# AR_-_Attack_Release.net
KiCad netlist of a schematic drawn in EAGLE
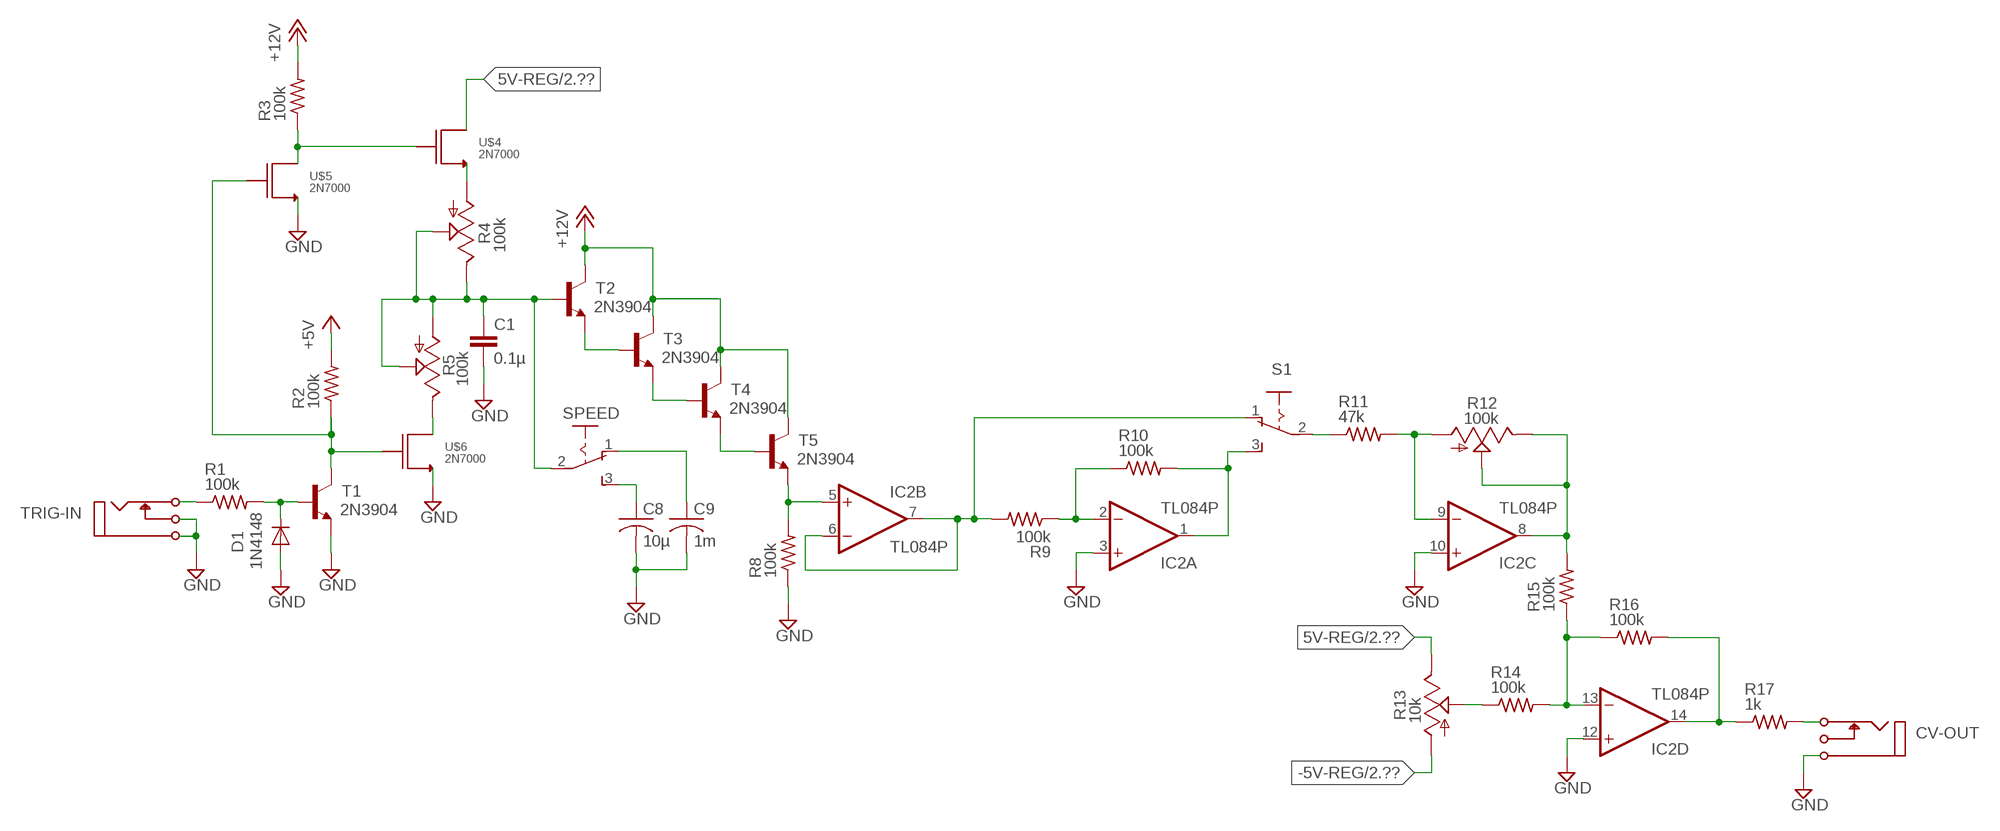
[diagram p0: schematic, sheet 1]
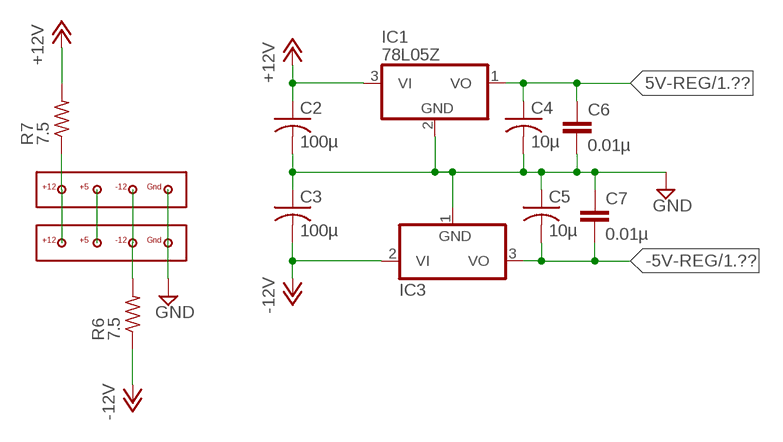
[diagram p1: schematic, sheet 2]

(export (version "E")
  (design (tool "Eeschema 10.0.6"))
  (components
    (comp (ref "C1")
      (value "0.1µ")
      (footprint "eagle-import:C2.5-2")
      (libsource (lib "eagle-import") (part "C2.5/2"))
    )
    (comp (ref "C8")
      (value "10µ")
      (footprint "eagle-import:C025-050X050")
      (libsource (lib "eagle-import") (part "C-US025-050X050"))
    )
    (comp (ref "C9")
      (value "1m")
      (footprint "eagle-import:C025-050X050")
      (libsource (lib "eagle-import") (part "C-US025-050X050"))
    )
    (comp (ref "CV-OUT")
      (value "I/O")
      (footprint "eagle-import:MONO_JACK")
      (libsource (lib "eagle-import") (part "MONO_JACK"))
    )
    (comp (ref "D1")
      (value "1N4148")
      (footprint "eagle-import:DO35-7")
      (libsource (lib "eagle-import") (part "1N4148DO35-7"))
    )
    (comp (ref "IC2")
      (value "TL084P")
      (footprint "eagle-import:DIL14")
      (libsource (lib "eagle-import") (part "TL084P"))
    )
    (comp (ref "R1")
      (value "100k")
      (footprint "eagle-import:0204_7")
      (libsource (lib "eagle-import") (part "R-US_0204/7"))
    )
    (comp (ref "R2")
      (value "100k")
      (footprint "eagle-import:0204_7")
      (libsource (lib "eagle-import") (part "R-US_0204/7"))
    )
    (comp (ref "R3")
      (value "100k")
      (footprint "eagle-import:0204_7")
      (libsource (lib "eagle-import") (part "R-US_0204/7"))
    )
    (comp (ref "R4")
      (value "100k")
      (footprint "eagle-import:B64Y")
      (libsource (lib "eagle-import") (part "TRIM_US-B64Y"))
    )
    (comp (ref "R5")
      (value "100k")
      (footprint "eagle-import:B64Y")
      (libsource (lib "eagle-import") (part "TRIM_US-B64Y"))
    )
    (comp (ref "R8")
      (value "100k")
      (footprint "eagle-import:0204_7")
      (libsource (lib "eagle-import") (part "R-US_0204/7"))
    )
    (comp (ref "R9")
      (value "100k")
      (footprint "eagle-import:0204_7")
      (libsource (lib "eagle-import") (part "R-US_0204/7"))
    )
    (comp (ref "R10")
      (value "100k")
      (footprint "eagle-import:0204_7")
      (libsource (lib "eagle-import") (part "R-US_0204/7"))
    )
    (comp (ref "R11")
      (value "47k")
      (footprint "eagle-import:0204_7")
      (libsource (lib "eagle-import") (part "R-US_0204/7"))
    )
    (comp (ref "R12")
      (value "100k")
      (footprint "eagle-import:B64Y")
      (libsource (lib "eagle-import") (part "TRIM_US-B64Y"))
    )
    (comp (ref "R13")
      (value "10k")
      (footprint "eagle-import:B64Y")
      (libsource (lib "eagle-import") (part "TRIM_US-B64Y"))
    )
    (comp (ref "R14")
      (value "100k")
      (footprint "eagle-import:0204_7")
      (libsource (lib "eagle-import") (part "R-US_0204/7"))
    )
    (comp (ref "R15")
      (value "100k")
      (footprint "eagle-import:0204_7")
      (libsource (lib "eagle-import") (part "R-US_0204/7"))
    )
    (comp (ref "R16")
      (value "100k")
      (footprint "eagle-import:0204_7")
      (libsource (lib "eagle-import") (part "R-US_0204/7"))
    )
    (comp (ref "R17")
      (value "1k")
      (footprint "eagle-import:0204_7")
      (libsource (lib "eagle-import") (part "R-US_0204/7"))
    )
    (comp (ref "S1")
      (value "255SB")
      (footprint "eagle-import:255SB")
      (libsource (lib "eagle-import") (part "255SB"))
    )
    (comp (ref "SPEED")
      (value "255SB")
      (footprint "eagle-import:255SB")
      (libsource (lib "eagle-import") (part "255SB"))
    )
    (comp (ref "T1")
      (value "2N3904")
      (footprint "eagle-import:TO92")
      (libsource (lib "eagle-import") (part "2N3904"))
    )
    (comp (ref "T2")
      (value "2N3904")
      (footprint "eagle-import:TO92")
      (libsource (lib "eagle-import") (part "2N3904"))
    )
    (comp (ref "T3")
      (value "2N3904")
      (footprint "eagle-import:TO92")
      (libsource (lib "eagle-import") (part "2N3904"))
    )
    (comp (ref "T4")
      (value "2N3904")
      (footprint "eagle-import:TO92")
      (libsource (lib "eagle-import") (part "2N3904"))
    )
    (comp (ref "T5")
      (value "2N3904")
      (footprint "eagle-import:TO92")
      (libsource (lib "eagle-import") (part "2N3904"))
    )
    (comp (ref "TRIG-IN")
      (value "I/O")
      (footprint "eagle-import:MONO_JACK")
      (libsource (lib "eagle-import") (part "MONO_JACK"))
    )
    (comp (ref "U$4")
      (value "2N7000")
      (footprint "eagle-import:2N7000")
      (libsource (lib "eagle-import") (part "2N7000"))
    )
    (comp (ref "U$5")
      (value "2N7000")
      (footprint "eagle-import:2N7000")
      (libsource (lib "eagle-import") (part "2N7000"))
    )
    (comp (ref "U$6")
      (value "2N7000")
      (footprint "eagle-import:2N7000")
      (libsource (lib "eagle-import") (part "2N7000"))
    )
    (comp (ref "C2")
      (value "100µ")
      (footprint "eagle-import:C025-050X050")
      (libsource (lib "eagle-import") (part "C-US025-050X050"))
    )
    (comp (ref "C3")
      (value "100µ")
      (footprint "eagle-import:C025-050X050")
      (libsource (lib "eagle-import") (part "C-US025-050X050"))
    )
    (comp (ref "C4")
      (value "10µ")
      (footprint "eagle-import:C025-050X050")
      (libsource (lib "eagle-import") (part "C-US025-050X050"))
    )
    (comp (ref "C5")
      (value "10µ")
      (footprint "eagle-import:C025-050X050")
      (libsource (lib "eagle-import") (part "C-US025-050X050"))
    )
    (comp (ref "C6")
      (value "0.01µ")
      (footprint "eagle-import:C2.5-2")
      (libsource (lib "eagle-import") (part "C2.5/2"))
    )
    (comp (ref "C7")
      (value "0.01µ")
      (footprint "eagle-import:C2.5-2")
      (libsource (lib "eagle-import") (part "C2.5/2"))
    )
    (comp (ref "IC1")
      (value "78L05Z")
      (footprint "eagle-import:TO92")
      (libsource (lib "eagle-import") (part "78ZL05"))
    )
    (comp (ref "IC3")
      (value "79L05Z")
      (footprint "eagle-import:TO92")
      (libsource (lib "eagle-import") (part "79ZL05"))
    )
    (comp (ref "R6")
      (value "7.5")
      (footprint "eagle-import:0204_7")
      (libsource (lib "eagle-import") (part "R-US_0204/7"))
    )
    (comp (ref "R7")
      (value "7.5")
      (footprint "eagle-import:0204_7")
      (libsource (lib "eagle-import") (part "R-US_0204/7"))
    )
    (comp (ref "U$3")
      (value "POWER_CONNECTOR_4_RGBB")
      (footprint "eagle-import:POWER_CONNECTOR_4_RGBB")
      (libsource (lib "eagle-import") (part "POWER_CONNECTOR_4_RGBB"))
    )
    (comp (ref "U$7")
      (value "POWER_CONNECTOR_4_RGBB")
      (footprint "eagle-import:POWER_CONNECTOR_4_RGBB")
      (libsource (lib "eagle-import") (part "POWER_CONNECTOR_4_RGBB"))
    )
  )
  (nets
    (net (code "1") (name "+5V") (class "Default")
      (node (ref "R2") (pin "2") (pinfunction "2_2") (pintype "passive"))
    )
    (net (code "2") (name "+12V") (class "Default")
      (node (ref "C2") (pin "1") (pinfunction "1_1") (pintype "passive"))
      (node (ref "IC1") (pin "3") (pinfunction "VI_3") (pintype "input"))
      (node (ref "R3") (pin "2") (pinfunction "2_2") (pintype "passive"))
      (node (ref "R7") (pin "2") (pinfunction "2_2") (pintype "passive"))
      (node (ref "T2") (pin "1") (pinfunction "C_1") (pintype "passive"))
      (node (ref "T3") (pin "1") (pinfunction "C_1") (pintype "passive"))
      (node (ref "T4") (pin "1") (pinfunction "C_1") (pintype "passive"))
      (node (ref "T5") (pin "1") (pinfunction "C_1") (pintype "passive"))
    )
    (net (code "3") (name "-5V-REG") (class "Default")
      (node (ref "C5") (pin "2") (pinfunction "2_2") (pintype "passive"))
      (node (ref "C7") (pin "2") (pinfunction "2_2") (pintype "passive"))
      (node (ref "IC3") (pin "3") (pinfunction "VO_3") (pintype "passive"))
      (node (ref "R13") (pin "A") (pinfunction "A_A") (pintype "passive"))
    )
    (net (code "4") (name "-12V") (class "Default")
      (node (ref "C3") (pin "2") (pinfunction "2_2") (pintype "passive"))
      (node (ref "IC3") (pin "2") (pinfunction "VI_2") (pintype "input"))
      (node (ref "R6") (pin "1") (pinfunction "1_1") (pintype "passive"))
    )
    (net (code "5") (name "5V-REG") (class "Default")
      (node (ref "C4") (pin "1") (pinfunction "1_1") (pintype "passive"))
      (node (ref "C6") (pin "1") (pinfunction "1_1") (pintype "passive"))
      (node (ref "IC1") (pin "1") (pinfunction "VO_1") (pintype "passive"))
      (node (ref "R13") (pin "E") (pinfunction "E_E") (pintype "passive"))
      (node (ref "U$4") (pin "D") (pinfunction "D_D") (pintype "bidirectional"))
    )
    (net (code "6") (name "GND") (class "Default")
      (node (ref "C1") (pin "2") (pinfunction "2_2") (pintype "passive"))
      (node (ref "C2") (pin "2") (pinfunction "2_2") (pintype "passive"))
      (node (ref "C3") (pin "1") (pinfunction "1_1") (pintype "passive"))
      (node (ref "C4") (pin "2") (pinfunction "2_2") (pintype "passive"))
      (node (ref "C5") (pin "1") (pinfunction "1_1") (pintype "passive"))
      (node (ref "C6") (pin "2") (pinfunction "2_2") (pintype "passive"))
      (node (ref "C7") (pin "1") (pinfunction "1_1") (pintype "passive"))
      (node (ref "C8") (pin "2") (pinfunction "2_2") (pintype "passive"))
      (node (ref "C9") (pin "2") (pinfunction "2_2") (pintype "passive"))
      (node (ref "CV-OUT") (pin "P$1") (pinfunction "P$1_P$1") (pintype "bidirectional"))
      (node (ref "D1") (pin "A") (pinfunction "A_A") (pintype "passive"))
      (node (ref "IC1") (pin "2") (pinfunction "GND_2") (pintype "passive"))
      (node (ref "IC2") (pin "10") (pinfunction "+IN_10") (pintype "input"))
      (node (ref "IC2") (pin "12") (pinfunction "+IN_12") (pintype "input"))
      (node (ref "IC2") (pin "3") (pinfunction "+IN_3") (pintype "input"))
      (node (ref "IC3") (pin "1") (pinfunction "GND_1") (pintype "passive"))
      (node (ref "R8") (pin "1") (pinfunction "1_1") (pintype "passive"))
      (node (ref "T1") (pin "3") (pinfunction "E_3") (pintype "passive"))
      (node (ref "TRIG-IN") (pin "P$1") (pinfunction "P$1_P$1") (pintype "bidirectional"))
      (node (ref "TRIG-IN") (pin "P$3") (pinfunction "P3_P$3") (pintype "bidirectional"))
      (node (ref "U$3") (pin "GND") (pinfunction "GND_GND") (pintype "bidirectional"))
      (node (ref "U$5") (pin "S") (pinfunction "S_S") (pintype "bidirectional"))
      (node (ref "U$6") (pin "S") (pinfunction "S_S") (pintype "bidirectional"))
      (node (ref "U$7") (pin "GND") (pinfunction "GND_GND") (pintype "bidirectional"))
    )
    (net (code "7") (name "Net-(CV-OUT-P2)") (class "Default")
      (node (ref "CV-OUT") (pin "P$2") (pinfunction "P2_P$2") (pintype "bidirectional"))
      (node (ref "R17") (pin "2") (pinfunction "2_2") (pintype "passive"))
    )
    (net (code "8") (name "Net-(IC2A--IN)") (class "Default")
      (node (ref "IC2") (pin "2") (pinfunction "-IN_2") (pintype "input"))
      (node (ref "R10") (pin "1") (pinfunction "1_1") (pintype "passive"))
      (node (ref "R9") (pin "1") (pinfunction "1_1") (pintype "passive"))
    )
    (net (code "9") (name "Net-(IC2A-OUT)") (class "Default")
      (node (ref "IC2") (pin "1") (pinfunction "OUT_1") (pintype "output"))
      (node (ref "R10") (pin "2") (pinfunction "2_2") (pintype "passive"))
      (node (ref "S1") (pin "3") (pinfunction "S_3") (pintype "passive"))
    )
    (net (code "10") (name "Net-(IC2B-+IN)") (class "Default")
      (node (ref "IC2") (pin "5") (pinfunction "+IN_5") (pintype "input"))
      (node (ref "R8") (pin "2") (pinfunction "2_2") (pintype "passive"))
      (node (ref "T5") (pin "3") (pinfunction "E_3") (pintype "passive"))
    )
    (net (code "11") (name "Net-(IC2B--IN)") (class "Default")
      (node (ref "IC2") (pin "6") (pinfunction "-IN_6") (pintype "input"))
      (node (ref "IC2") (pin "7") (pinfunction "OUT_7") (pintype "output"))
      (node (ref "R9") (pin "2") (pinfunction "2_2") (pintype "passive"))
      (node (ref "S1") (pin "1") (pinfunction "O_1") (pintype "passive"))
    )
    (net (code "12") (name "Net-(IC2C--IN)") (class "Default")
      (node (ref "IC2") (pin "9") (pinfunction "-IN_9") (pintype "input"))
      (node (ref "R11") (pin "2") (pinfunction "2_2") (pintype "passive"))
      (node (ref "R12") (pin "A") (pinfunction "A_A") (pintype "passive"))
    )
    (net (code "13") (name "Net-(IC2C-OUT)") (class "Default")
      (node (ref "IC2") (pin "8") (pinfunction "OUT_8") (pintype "output"))
      (node (ref "R12") (pin "E") (pinfunction "E_E") (pintype "passive"))
      (node (ref "R12") (pin "S") (pinfunction "S_S") (pintype "passive"))
      (node (ref "R15") (pin "2") (pinfunction "2_2") (pintype "passive"))
    )
    (net (code "14") (name "Net-(IC2D--IN)") (class "Default")
      (node (ref "IC2") (pin "13") (pinfunction "-IN_13") (pintype "input"))
      (node (ref "R14") (pin "2") (pinfunction "2_2") (pintype "passive"))
      (node (ref "R15") (pin "1") (pinfunction "1_1") (pintype "passive"))
      (node (ref "R16") (pin "1") (pinfunction "1_1") (pintype "passive"))
    )
    (net (code "15") (name "Net-(IC2D-OUT)") (class "Default")
      (node (ref "IC2") (pin "14") (pinfunction "OUT_14") (pintype "output"))
      (node (ref "R16") (pin "2") (pinfunction "2_2") (pintype "passive"))
      (node (ref "R17") (pin "1") (pinfunction "1_1") (pintype "passive"))
    )
    (net (code "16") (name "Net-(R3-Pad1)") (class "Default")
      (node (ref "R3") (pin "1") (pinfunction "1_1") (pintype "passive"))
      (node (ref "U$4") (pin "G") (pinfunction "G_G") (pintype "bidirectional"))
      (node (ref "U$5") (pin "D") (pinfunction "D_D") (pintype "bidirectional"))
    )
    (net (code "17") (name "Net-(R4-PadA)") (class "Default")
      (node (ref "R4") (pin "A") (pinfunction "A_A") (pintype "passive"))
      (node (ref "U$4") (pin "S") (pinfunction "S_S") (pintype "bidirectional"))
    )
    (net (code "18") (name "Net-(R5-PadE)") (class "Default")
      (node (ref "R5") (pin "E") (pinfunction "E_E") (pintype "passive"))
      (node (ref "U$6") (pin "D") (pinfunction "D_D") (pintype "bidirectional"))
    )
    (net (code "19") (name "Net-(R6-Pad2)") (class "Default")
      (node (ref "R6") (pin "2") (pinfunction "2_2") (pintype "passive"))
      (node (ref "U$3") (pin "-12") (pinfunction "-12_-12") (pintype "bidirectional"))
      (node (ref "U$7") (pin "-12") (pinfunction "-12_-12") (pintype "bidirectional"))
    )
    (net (code "20") (name "Net-(R7-Pad1)") (class "Default")
      (node (ref "R7") (pin "1") (pinfunction "1_1") (pintype "passive"))
      (node (ref "U$3") (pin "+12") (pinfunction "+12_+12") (pintype "bidirectional"))
      (node (ref "U$7") (pin "+12") (pinfunction "+12_+12") (pintype "bidirectional"))
    )
    (net (code "21") (name "Net-(R13-PadS)") (class "Default")
      (node (ref "R13") (pin "S") (pinfunction "S_S") (pintype "passive"))
      (node (ref "R14") (pin "1") (pinfunction "1_1") (pintype "passive"))
    )
    (net (code "22") (name "Net-(S1-P)") (class "Default")
      (node (ref "R11") (pin "1") (pinfunction "1_1") (pintype "passive"))
      (node (ref "S1") (pin "2") (pinfunction "P_2") (pintype "passive"))
    )
    (net (code "23") (name "Net-(SPEED-O)") (class "Default")
      (node (ref "C9") (pin "1") (pinfunction "1_1") (pintype "passive"))
      (node (ref "SPEED") (pin "1") (pinfunction "O_1") (pintype "passive"))
    )
    (net (code "24") (name "Net-(SPEED-P)") (class "Default")
      (node (ref "C1") (pin "1") (pinfunction "1_1") (pintype "passive"))
      (node (ref "R4") (pin "E") (pinfunction "E_E") (pintype "passive"))
      (node (ref "R4") (pin "S") (pinfunction "S_S") (pintype "passive"))
      (node (ref "R5") (pin "A") (pinfunction "A_A") (pintype "passive"))
      (node (ref "R5") (pin "S") (pinfunction "S_S") (pintype "passive"))
      (node (ref "SPEED") (pin "2") (pinfunction "P_2") (pintype "passive"))
      (node (ref "T2") (pin "2") (pinfunction "B_2") (pintype "passive"))
    )
    (net (code "25") (name "Net-(SPEED-S)") (class "Default")
      (node (ref "C8") (pin "1") (pinfunction "1_1") (pintype "passive"))
      (node (ref "SPEED") (pin "3") (pinfunction "S_3") (pintype "passive"))
    )
    (net (code "26") (name "Net-(T1-B)") (class "Default")
      (node (ref "D1") (pin "C") (pinfunction "C_C") (pintype "passive"))
      (node (ref "R1") (pin "2") (pinfunction "2_2") (pintype "passive"))
      (node (ref "T1") (pin "2") (pinfunction "B_2") (pintype "passive"))
    )
    (net (code "27") (name "Net-(T1-C)") (class "Default")
      (node (ref "R2") (pin "1") (pinfunction "1_1") (pintype "passive"))
      (node (ref "T1") (pin "1") (pinfunction "C_1") (pintype "passive"))
      (node (ref "U$5") (pin "G") (pinfunction "G_G") (pintype "bidirectional"))
      (node (ref "U$6") (pin "G") (pinfunction "G_G") (pintype "bidirectional"))
    )
    (net (code "28") (name "Net-(T2-E)") (class "Default")
      (node (ref "T2") (pin "3") (pinfunction "E_3") (pintype "passive"))
      (node (ref "T3") (pin "2") (pinfunction "B_2") (pintype "passive"))
    )
    (net (code "29") (name "Net-(T3-E)") (class "Default")
      (node (ref "T3") (pin "3") (pinfunction "E_3") (pintype "passive"))
      (node (ref "T4") (pin "2") (pinfunction "B_2") (pintype "passive"))
    )
    (net (code "30") (name "Net-(T4-E)") (class "Default")
      (node (ref "T4") (pin "3") (pinfunction "E_3") (pintype "passive"))
      (node (ref "T5") (pin "2") (pinfunction "B_2") (pintype "passive"))
    )
    (net (code "31") (name "Net-(TRIG-IN-P2)") (class "Default")
      (node (ref "R1") (pin "1") (pinfunction "1_1") (pintype "passive"))
      (node (ref "TRIG-IN") (pin "P$2") (pinfunction "P2_P$2") (pintype "bidirectional"))
    )
    (net (code "32") (name "Net-(U$3-Pad+5)") (class "Default")
      (node (ref "U$3") (pin "+5") (pinfunction "+5_+5") (pintype "bidirectional"))
      (node (ref "U$7") (pin "+5") (pinfunction "+5_+5") (pintype "bidirectional"))
    )
    (net (code "33") (name "unconnected-(CV-OUT-P3-PadP$3)") (class "Default")
      (node (ref "CV-OUT") (pin "P$3") (pinfunction "P3_P$3") (pintype "bidirectional"))
    )
  )
)
